# 05_FPGA_A.net
KiCad netlist of a schematic drawn in Altium Designer
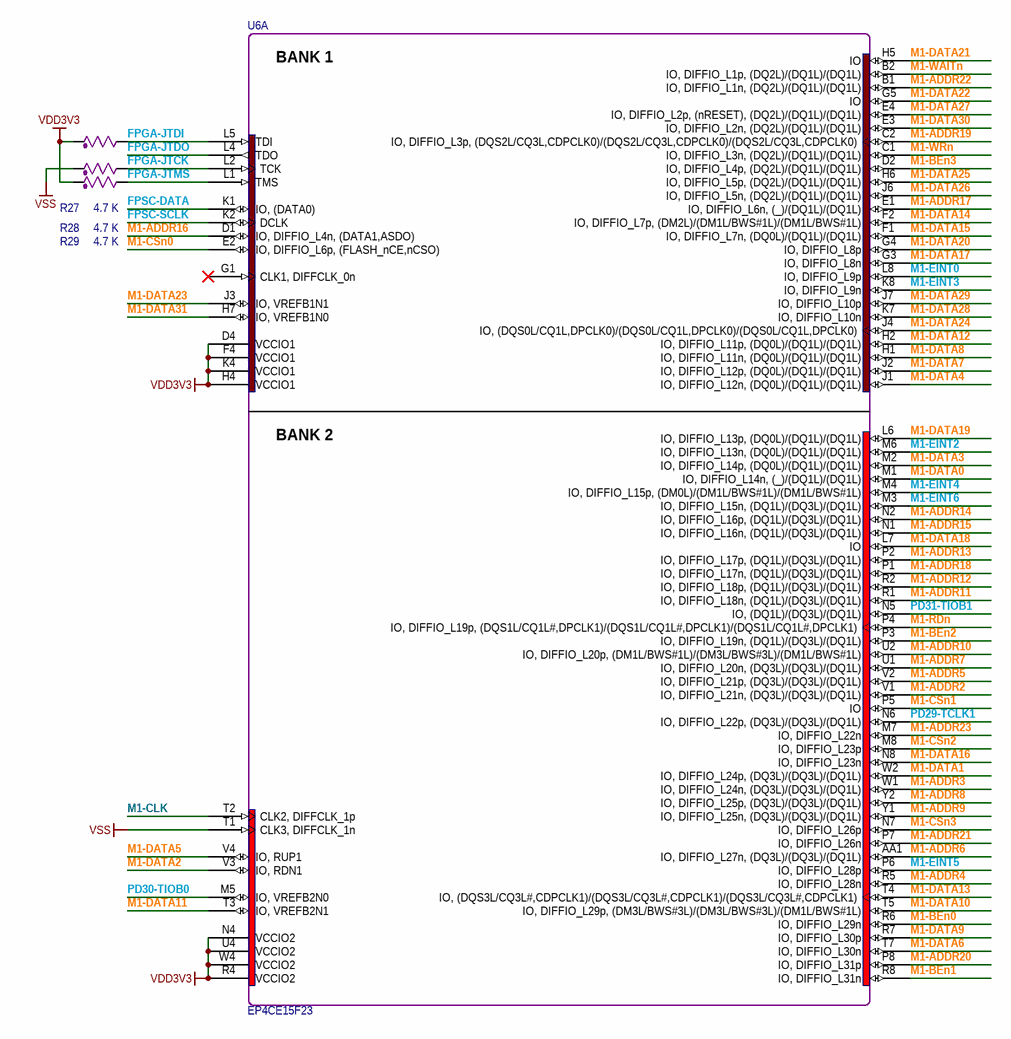
[diagram p0: 05_FPGA_A.SchDoc]

(export (version "E")
  (design (tool "Eeschema 10.0.6"))
  (components
    (comp (ref "R27")
      (value "4.7 K")
      (footprint "0402A2")
      (description "Normal Resistor")
      (fields
        (field (name "PARTNUMBER") "0")
        (field (name "DESIGNER") "shyul")
        (field (name "PUBLISHER") "Cowin")
      )
      (libsource (lib "Basc_1_Passive") (part "RES"))
    )
    (comp (ref "R28")
      (value "4.7 K")
      (footprint "0402A2")
      (description "Normal Resistor")
      (fields
        (field (name "PARTNUMBER") "0")
        (field (name "DESIGNER") "shyul")
        (field (name "PUBLISHER") "Cowin")
      )
      (libsource (lib "Basc_1_Passive") (part "RES"))
    )
    (comp (ref "R29")
      (value "4.7 K")
      (footprint "0402A2")
      (description "Normal Resistor")
      (fields
        (field (name "PARTNUMBER") "0")
        (field (name "DESIGNER") "shyul")
        (field (name "PUBLISHER") "Cowin")
      )
      (libsource (lib "Basc_1_Passive") (part "RES"))
    )
    (comp (ref "U6")
      (value "EP4CE15F23")
      (footprint "FBGA-484")
      (description "Cyclone IV EP4CE15F23 FPGA")
      (fields
        (field (name "PARTNUMBER") "EP4CE15F23C8N")
        (field (name "DESIGNER") "shyul")
        (field (name "PUBLISHER") "Cowin")
      )
      (libsource (lib "PCB_XEM-S91") (part "EP4CE15F23"))
    )
  )
  (nets
    (net (code "1") (name "/FPGA-JTCK") (class "Default")
      (node (ref "R28") (pin "1") (pinfunction "1_1") (pintype "passive"))
      (node (ref "U6") (pin "L2") (pinfunction "TCK_L2") (pintype "input"))
    )
    (net (code "2") (name "/FPGA-JTDI") (class "Default")
      (node (ref "R27") (pin "1") (pinfunction "1_1") (pintype "passive"))
      (node (ref "U6") (pin "L5") (pinfunction "TDI_L5") (pintype "input"))
    )
    (net (code "3") (name "/FPGA-JTDO") (class "Default")
      (node (ref "U6") (pin "L4") (pinfunction "TDO_L4") (pintype "output"))
    )
    (net (code "4") (name "/FPGA-JTMS") (class "Default")
      (node (ref "R29") (pin "1") (pinfunction "1_1") (pintype "passive"))
      (node (ref "U6") (pin "L1") (pinfunction "TMS_L1") (pintype "input"))
    )
    (net (code "5") (name "/FPSC-DATA") (class "Default")
      (node (ref "U6") (pin "K1") (pinfunction "IO,_(DATA0)_K1") (pintype "bidirectional"))
    )
    (net (code "6") (name "/FPSC-SCLK") (class "Default")
      (node (ref "U6") (pin "K2") (pinfunction "DCLK_K2") (pintype "bidirectional"))
    )
    (net (code "7") (name "/M1-ADDR2") (class "Default")
      (node (ref "U6") (pin "V1") (pinfunction "IO,_DIFFIO_L21n,_(DQ3L)/(DQ3L)/(DQ1L)_V1") (pintype "bidirectional"))
    )
    (net (code "8") (name "/M1-ADDR3") (class "Default")
      (node (ref "U6") (pin "W1") (pinfunction "IO,_DIFFIO_L24n,_(DQ3L)/(DQ3L)/(DQ1L)_W1") (pintype "bidirectional"))
    )
    (net (code "9") (name "/M1-ADDR4") (class "Default")
      (node (ref "U6") (pin "R5") (pinfunction "IO,_DIFFIO_L28n_R5") (pintype "bidirectional"))
    )
    (net (code "10") (name "/M1-ADDR5") (class "Default")
      (node (ref "U6") (pin "V2") (pinfunction "IO,_DIFFIO_L21p,_(DQ3L)/(DQ3L)/(DQ1L)_V2") (pintype "bidirectional"))
    )
    (net (code "11") (name "/M1-ADDR6") (class "Default")
      (node (ref "U6") (pin "AA1") (pinfunction "IO,_DIFFIO_L27n,_(DQ3L)/(DQ3L)/(DQ1L)_AA1") (pintype "bidirectional"))
    )
    (net (code "12") (name "/M1-ADDR7") (class "Default")
      (node (ref "U6") (pin "U1") (pinfunction "IO,_DIFFIO_L20n,_(DQ3L)/(DQ3L)/(DQ1L)_U1") (pintype "bidirectional"))
    )
    (net (code "13") (name "/M1-ADDR8") (class "Default")
      (node (ref "U6") (pin "Y2") (pinfunction "IO,_DIFFIO_L25p,_(DQ3L)/(DQ3L)/(DQ1L)_Y2") (pintype "bidirectional"))
    )
    (net (code "14") (name "/M1-ADDR9") (class "Default")
      (node (ref "U6") (pin "Y1") (pinfunction "IO,_DIFFIO_L25n,_(DQ3L)/(DQ3L)/(DQ1L)_Y1") (pintype "bidirectional"))
    )
    (net (code "15") (name "/M1-ADDR10") (class "Default")
      (node (ref "U6") (pin "U2") (pinfunction "IO,_DIFFIO_L20p,_(DM1L/BWS#1L)/(DM3L/BWS#3L)/(DM1L/BWS#1L)_U2") (pintype "bidirectional"))
    )
    (net (code "16") (name "/M1-ADDR11") (class "Default")
      (node (ref "U6") (pin "R1") (pinfunction "IO,_DIFFIO_L18n,_(DQ1L)/(DQ3L)/(DQ1L)_R1") (pintype "bidirectional"))
    )
    (net (code "17") (name "/M1-ADDR12") (class "Default")
      (node (ref "U6") (pin "R2") (pinfunction "IO,_DIFFIO_L18p,_(DQ1L)/(DQ3L)/(DQ1L)_R2") (pintype "bidirectional"))
    )
    (net (code "18") (name "/M1-ADDR13") (class "Default")
      (node (ref "U6") (pin "P2") (pinfunction "IO,_DIFFIO_L17p,_(DQ1L)/(DQ3L)/(DQ1L)_P2") (pintype "bidirectional"))
    )
    (net (code "19") (name "/M1-ADDR14") (class "Default")
      (node (ref "U6") (pin "N2") (pinfunction "IO,_DIFFIO_L16p,_(DQ1L)/(DQ3L)/(DQ1L)_N2") (pintype "bidirectional"))
    )
    (net (code "20") (name "/M1-ADDR15") (class "Default")
      (node (ref "U6") (pin "N1") (pinfunction "IO,_DIFFIO_L16n,_(DQ1L)/(DQ3L)/(DQ1L)_N1") (pintype "bidirectional"))
    )
    (net (code "21") (name "/M1-ADDR16") (class "Default")
      (node (ref "U6") (pin "D1") (pinfunction "IO,_DIFFIO_L4n,_(DATA1,ASDO)_D1") (pintype "bidirectional"))
    )
    (net (code "22") (name "/M1-ADDR17") (class "Default")
      (node (ref "U6") (pin "E1") (pinfunction "IO,_DIFFIO_L6n,_(_)/(DQ1L)/(DQ1L)_E1") (pintype "bidirectional"))
    )
    (net (code "23") (name "/M1-ADDR18") (class "Default")
      (node (ref "U6") (pin "P1") (pinfunction "IO,_DIFFIO_L17n,_(DQ1L)/(DQ3L)/(DQ1L)_P1") (pintype "bidirectional"))
    )
    (net (code "24") (name "/M1-ADDR19") (class "Default")
      (node (ref "U6") (pin "C2") (pinfunction "IO,_DIFFIO_L3p,_(DQS2L/CQ3L,CDPCLK0)/(DQS2L/CQ3L,CDPCLK0)/(DQS2L/CQ3L,CDPCLK0)_C2") (pintype "bidirectional"))
    )
    (net (code "25") (name "/M1-ADDR20") (class "Default")
      (node (ref "U6") (pin "P8") (pinfunction "IO,_DIFFIO_L31p_P8") (pintype "bidirectional"))
    )
    (net (code "26") (name "/M1-ADDR21") (class "Default")
      (node (ref "U6") (pin "P7") (pinfunction "IO,_DIFFIO_L26n_P7") (pintype "bidirectional"))
    )
    (net (code "27") (name "/M1-ADDR22") (class "Default")
      (node (ref "U6") (pin "B1") (pinfunction "IO,_DIFFIO_L1n,_(DQ2L)/(DQ1L)/(DQ1L)_B1") (pintype "bidirectional"))
    )
    (net (code "28") (name "/M1-ADDR23") (class "Default")
      (node (ref "U6") (pin "M7") (pinfunction "IO,_DIFFIO_L22n_M7") (pintype "bidirectional"))
    )
    (net (code "29") (name "/M1-BEn0") (class "Default")
      (node (ref "U6") (pin "R6") (pinfunction "IO,_DIFFIO_L29n_R6") (pintype "bidirectional"))
    )
    (net (code "30") (name "/M1-BEn1") (class "Default")
      (node (ref "U6") (pin "R8") (pinfunction "IO,_DIFFIO_L31n_R8") (pintype "bidirectional"))
    )
    (net (code "31") (name "/M1-BEn2") (class "Default")
      (node (ref "U6") (pin "P3") (pinfunction "IO,_DIFFIO_L19n,_(DQ1L)/(DQ3L)/(DQ1L)_P3") (pintype "bidirectional"))
    )
    (net (code "32") (name "/M1-BEn3") (class "Default")
      (node (ref "U6") (pin "D2") (pinfunction "IO,_DIFFIO_L4p,_(DQ2L)/(DQ1L)/(DQ1L)_D2") (pintype "bidirectional"))
    )
    (net (code "33") (name "/M1-CLK") (class "Default")
      (node (ref "U6") (pin "T2") (pinfunction "CLK2,_DIFFCLK_1p_T2") (pintype "input"))
    )
    (net (code "34") (name "/M1-CSn0") (class "Default")
      (node (ref "U6") (pin "E2") (pinfunction "IO,_DIFFIO_L6p,_(FLASH_nCE,nCSO)_E2") (pintype "bidirectional"))
    )
    (net (code "35") (name "/M1-CSn1") (class "Default")
      (node (ref "U6") (pin "P5") (pinfunction "IO_P5") (pintype "bidirectional"))
    )
    (net (code "36") (name "/M1-CSn2") (class "Default")
      (node (ref "U6") (pin "M8") (pinfunction "IO,_DIFFIO_L23p_M8") (pintype "bidirectional"))
    )
    (net (code "37") (name "/M1-CSn3") (class "Default")
      (node (ref "U6") (pin "N7") (pinfunction "IO,_DIFFIO_L26p_N7") (pintype "bidirectional"))
    )
    (net (code "38") (name "/M1-DATA0") (class "Default")
      (node (ref "U6") (pin "M1") (pinfunction "IO,_DIFFIO_L14n,_(_)/(DQ1L)/(DQ1L)_M1") (pintype "bidirectional"))
    )
    (net (code "39") (name "/M1-DATA1") (class "Default")
      (node (ref "U6") (pin "W2") (pinfunction "IO,_DIFFIO_L24p,_(DQ3L)/(DQ3L)/(DQ1L)_W2") (pintype "bidirectional"))
    )
    (net (code "40") (name "/M1-DATA2") (class "Default")
      (node (ref "U6") (pin "V3") (pinfunction "IO,_RDN1_V3") (pintype "bidirectional"))
    )
    (net (code "41") (name "/M1-DATA3") (class "Default")
      (node (ref "U6") (pin "M2") (pinfunction "IO,_DIFFIO_L14p,_(DQ0L)/(DQ1L)/(DQ1L)_M2") (pintype "bidirectional"))
    )
    (net (code "42") (name "/M1-DATA4") (class "Default")
      (node (ref "U6") (pin "J1") (pinfunction "IO,_DIFFIO_L12n,_(DQ0L)/(DQ1L)/(DQ1L)_J1") (pintype "bidirectional"))
    )
    (net (code "43") (name "/M1-DATA5") (class "Default")
      (node (ref "U6") (pin "V4") (pinfunction "IO,_RUP1_V4") (pintype "bidirectional"))
    )
    (net (code "44") (name "/M1-DATA6") (class "Default")
      (node (ref "U6") (pin "T7") (pinfunction "IO,_DIFFIO_L30n_T7") (pintype "bidirectional"))
    )
    (net (code "45") (name "/M1-DATA7") (class "Default")
      (node (ref "U6") (pin "J2") (pinfunction "IO,_DIFFIO_L12p,_(DQ0L)/(DQ1L)/(DQ1L)_J2") (pintype "bidirectional"))
    )
    (net (code "46") (name "/M1-DATA8") (class "Default")
      (node (ref "U6") (pin "H1") (pinfunction "IO,_DIFFIO_L11n,_(DQ0L)/(DQ1L)/(DQ1L)_H1") (pintype "bidirectional"))
    )
    (net (code "47") (name "/M1-DATA9") (class "Default")
      (node (ref "U6") (pin "R7") (pinfunction "IO,_DIFFIO_L30p_R7") (pintype "bidirectional"))
    )
    (net (code "48") (name "/M1-DATA10") (class "Default")
      (node (ref "U6") (pin "T5") (pinfunction "IO,_DIFFIO_L29p,_(DM3L/BWS#3L)/(DM3L/BWS#3L)/(DM1L/BWS#1L)_T5") (pintype "bidirectional"))
    )
    (net (code "49") (name "/M1-DATA11") (class "Default")
      (node (ref "U6") (pin "T3") (pinfunction "IO,_VREFB2N1_T3") (pintype "bidirectional"))
    )
    (net (code "50") (name "/M1-DATA12") (class "Default")
      (node (ref "U6") (pin "H2") (pinfunction "IO,_DIFFIO_L11p,_(DQ0L)/(DQ1L)/(DQ1L)_H2") (pintype "bidirectional"))
    )
    (net (code "51") (name "/M1-DATA13") (class "Default")
      (node (ref "U6") (pin "T4") (pinfunction "IO,_(DQS3L/CQ3L#,CDPCLK1)/(DQS3L/CQ3L#,CDPCLK1)/(DQS3L/CQ3L#,CDPCLK1)_T4") (pintype "bidirectional"))
    )
    (net (code "52") (name "/M1-DATA14") (class "Default")
      (node (ref "U6") (pin "F2") (pinfunction "IO,_DIFFIO_L7p,_(DM2L)/(DM1L/BWS#1L)/(DM1L/BWS#1L)_F2") (pintype "bidirectional"))
    )
    (net (code "53") (name "/M1-DATA15") (class "Default")
      (node (ref "U6") (pin "F1") (pinfunction "IO,_DIFFIO_L7n,_(DQ0L)/(DQ1L)/(DQ1L)_F1") (pintype "bidirectional"))
    )
    (net (code "54") (name "/M1-DATA16") (class "Default")
      (node (ref "U6") (pin "N8") (pinfunction "IO,_DIFFIO_L23n_N8") (pintype "bidirectional"))
    )
    (net (code "55") (name "/M1-DATA17") (class "Default")
      (node (ref "U6") (pin "G3") (pinfunction "IO,_DIFFIO_L8n_G3") (pintype "bidirectional"))
    )
    (net (code "56") (name "/M1-DATA18") (class "Default")
      (node (ref "U6") (pin "L7") (pinfunction "IO_L7") (pintype "bidirectional"))
    )
    (net (code "57") (name "/M1-DATA19") (class "Default")
      (node (ref "U6") (pin "L6") (pinfunction "IO,_DIFFIO_L13p,_(DQ0L)/(DQ1L)/(DQ1L)_L6") (pintype "bidirectional"))
    )
    (net (code "58") (name "/M1-DATA20") (class "Default")
      (node (ref "U6") (pin "G4") (pinfunction "IO,_DIFFIO_L8p_G4") (pintype "bidirectional"))
    )
    (net (code "59") (name "/M1-DATA21") (class "Default")
      (node (ref "U6") (pin "H5") (pinfunction "IO_H5") (pintype "bidirectional"))
    )
    (net (code "60") (name "/M1-DATA22") (class "Default")
      (node (ref "U6") (pin "G5") (pinfunction "IO_G5") (pintype "bidirectional"))
    )
    (net (code "61") (name "/M1-DATA23") (class "Default")
      (node (ref "U6") (pin "J3") (pinfunction "IO,_VREFB1N1_J3") (pintype "bidirectional"))
    )
    (net (code "62") (name "/M1-DATA24") (class "Default")
      (node (ref "U6") (pin "J4") (pinfunction "IO,_(DQS0L/CQ1L,DPCLK0)/(DQS0L/CQ1L,DPCLK0)/(DQS0L/CQ1L,DPCLK0)_J4") (pintype "bidirectional"))
    )
    (net (code "63") (name "/M1-DATA25") (class "Default")
      (node (ref "U6") (pin "H6") (pinfunction "IO,_DIFFIO_L5p,_(DQ2L)/(DQ1L)/(DQ1L)_H6") (pintype "bidirectional"))
    )
    (net (code "64") (name "/M1-DATA26") (class "Default")
      (node (ref "U6") (pin "J6") (pinfunction "IO,_DIFFIO_L5n,_(DQ2L)/(DQ1L)/(DQ1L)_J6") (pintype "bidirectional"))
    )
    (net (code "65") (name "/M1-DATA27") (class "Default")
      (node (ref "U6") (pin "E4") (pinfunction "IO,_DIFFIO_L2p,_(nRESET),_(DQ2L)/(DQ1L)/(DQ1L)_E4") (pintype "bidirectional"))
    )
    (net (code "66") (name "/M1-DATA28") (class "Default")
      (node (ref "U6") (pin "K7") (pinfunction "IO,_DIFFIO_L10n_K7") (pintype "bidirectional"))
    )
    (net (code "67") (name "/M1-DATA29") (class "Default")
      (node (ref "U6") (pin "J7") (pinfunction "IO,_DIFFIO_L10p_J7") (pintype "bidirectional"))
    )
    (net (code "68") (name "/M1-DATA30") (class "Default")
      (node (ref "U6") (pin "E3") (pinfunction "IO,_DIFFIO_L2n,_(DQ2L)/(DQ1L)/(DQ1L)_E3") (pintype "bidirectional"))
    )
    (net (code "69") (name "/M1-DATA31") (class "Default")
      (node (ref "U6") (pin "H7") (pinfunction "IO,_VREFB1N0_H7") (pintype "bidirectional"))
    )
    (net (code "70") (name "/M1-EINT0") (class "Default")
      (node (ref "U6") (pin "L8") (pinfunction "IO,_DIFFIO_L9p_L8") (pintype "bidirectional"))
    )
    (net (code "71") (name "/M1-EINT2") (class "Default")
      (node (ref "U6") (pin "M6") (pinfunction "IO,_DIFFIO_L13n,_(DQ0L)/(DQ1L)/(DQ1L)_M6") (pintype "bidirectional"))
    )
    (net (code "72") (name "/M1-EINT3") (class "Default")
      (node (ref "U6") (pin "K8") (pinfunction "IO,_DIFFIO_L9n_K8") (pintype "bidirectional"))
    )
    (net (code "73") (name "/M1-EINT4") (class "Default")
      (node (ref "U6") (pin "M4") (pinfunction "IO,_DIFFIO_L15p,_(DM0L)/(DM1L/BWS#1L)/(DM1L/BWS#1L)_M4") (pintype "bidirectional"))
    )
    (net (code "74") (name "/M1-EINT5") (class "Default")
      (node (ref "U6") (pin "P6") (pinfunction "IO,_DIFFIO_L28p_P6") (pintype "bidirectional"))
    )
    (net (code "75") (name "/M1-EINT6") (class "Default")
      (node (ref "U6") (pin "M3") (pinfunction "IO,_DIFFIO_L15n,_(DQ1L)/(DQ3L)/(DQ1L)_M3") (pintype "bidirectional"))
    )
    (net (code "76") (name "/M1-RDn") (class "Default")
      (node (ref "U6") (pin "P4") (pinfunction "IO,_DIFFIO_L19p,_(DQS1L/CQ1L#,DPCLK1)/(DQS1L/CQ1L#,DPCLK1)/(DQS1L/CQ1L#,DPCLK1)_P4") (pintype "bidirectional"))
    )
    (net (code "77") (name "/M1-WAITn") (class "Default")
      (node (ref "U6") (pin "B2") (pinfunction "IO,_DIFFIO_L1p,_(DQ2L)/(DQ1L)/(DQ1L)_B2") (pintype "bidirectional"))
    )
    (net (code "78") (name "/M1-WRn") (class "Default")
      (node (ref "U6") (pin "C1") (pinfunction "IO,_DIFFIO_L3n,_(DQ2L)/(DQ1L)/(DQ1L)_C1") (pintype "bidirectional"))
    )
    (net (code "79") (name "/PD29-TCLK1") (class "Default")
      (node (ref "U6") (pin "N6") (pinfunction "IO,_DIFFIO_L22p,_(DQ3L)/(DQ3L)/(DQ1L)_N6") (pintype "bidirectional"))
    )
    (net (code "80") (name "/PD30-TIOB0") (class "Default")
      (node (ref "U6") (pin "M5") (pinfunction "IO,_VREFB2N0_M5") (pintype "bidirectional"))
    )
    (net (code "81") (name "/PD31-TIOB1") (class "Default")
      (node (ref "U6") (pin "N5") (pinfunction "IO,_(DQ1L)/(DQ3L)/(DQ1L)_N5") (pintype "bidirectional"))
    )
    (net (code "82") (name "VDD3V3") (class "Default")
      (node (ref "R27") (pin "2") (pinfunction "2_2") (pintype "passive"))
      (node (ref "R29") (pin "2") (pinfunction "2_2") (pintype "passive"))
      (node (ref "U6") (pin "D4") (pinfunction "VCCIO1_D4") (pintype "power_in"))
      (node (ref "U6") (pin "F4") (pinfunction "VCCIO1_F4") (pintype "power_in"))
      (node (ref "U6") (pin "H4") (pinfunction "VCCIO1_H4") (pintype "power_in"))
      (node (ref "U6") (pin "K4") (pinfunction "VCCIO1_K4") (pintype "power_in"))
      (node (ref "U6") (pin "N4") (pinfunction "VCCIO2_N4") (pintype "power_in"))
      (node (ref "U6") (pin "R4") (pinfunction "VCCIO2_R4") (pintype "power_in"))
      (node (ref "U6") (pin "U4") (pinfunction "VCCIO2_U4") (pintype "power_in"))
      (node (ref "U6") (pin "W4") (pinfunction "VCCIO2_W4") (pintype "power_in"))
    )
    (net (code "83") (name "VSS") (class "Default")
      (node (ref "R28") (pin "2") (pinfunction "2_2") (pintype "passive"))
      (node (ref "U6") (pin "T1") (pinfunction "CLK3,_DIFFCLK_1n_T1") (pintype "input"))
    )
    (net (code "84") (name "unconnected-(U6A-CLK1,_DIFFCLK_0n-PadG1)") (class "Default")
      (node (ref "U6") (pin "G1") (pinfunction "CLK1,_DIFFCLK_0n_G1") (pintype "input+no_connect"))
    )
  )
)
